# Sheet1without_res.net
KiCad netlist of a schematic drawn in Altium Designer
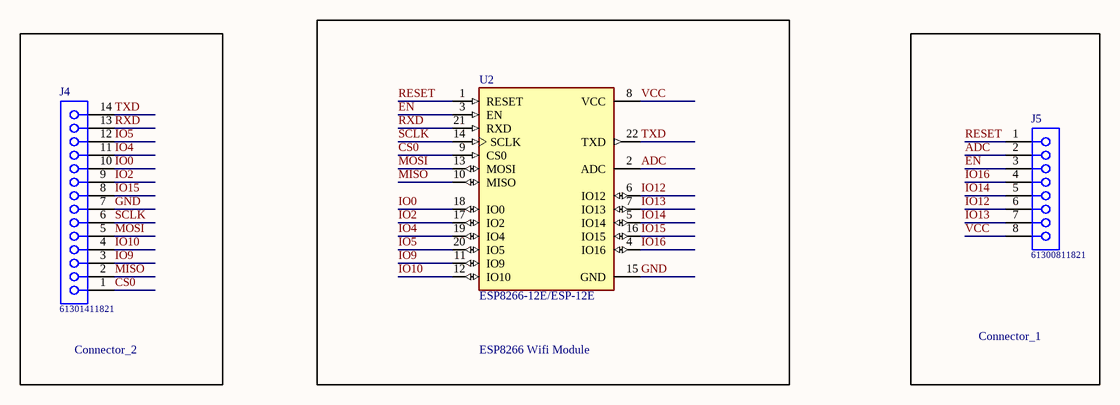
[diagram p0: Sheet1without_res.SchDoc]

(export (version "E")
  (design (tool "Eeschema 10.0.6"))
  (components
    (comp (ref "J4")
      (value "61301411821")
      (footprint "61301411821")
      (description "WR-PHD Socket Header, THT, pitch 2.54mm, Single Row, Vertical, 14p")
      (fields (field (name "MANUFACTURER") "Wurth Elektronik"))
      (libsource (lib "Altium_WR-PHD (rev20a) (2)") (part "61301411821"))
    )
    (comp (ref "J5")
      (value "61300811821")
      (footprint "61300811821")
      (description "WR-PHD Socket Header, THT, pitch 2.54mm, Single Row, Vertical, 8p")
      (fields (field (name "MANUFACTURER") "Wurth Elektronik"))
      (libsource (lib "Altium_WR-PHD (rev20a)") (part "61300811821"))
    )
    (comp (ref "U2")
      (value "ESP8266-12E/ESP-12E")
      (footprint "XCVR_ESP8266-12E/ESP-12E")
      (fields (field (name "MF") "AI-Thinker"))
      (libsource (lib "ESP8266-12E_ESP-12E") (part "ESP8266-12E/ESP-12E"))
    )
  )
  (nets
    (net (code "1") (name "/ADC") (class "Default")
      (node (ref "J5") (pin "2") (pinfunction "2_2") (pintype "passive"))
      (node (ref "U2") (pin "2") (pinfunction "ADC_2") (pintype "passive"))
    )
    (net (code "2") (name "/CS0") (class "Default")
      (node (ref "J4") (pin "1") (pinfunction "1_1") (pintype "passive"))
      (node (ref "U2") (pin "9") (pinfunction "CS0_9") (pintype "input"))
    )
    (net (code "3") (name "/EN") (class "Default")
      (node (ref "J5") (pin "3") (pinfunction "3_3") (pintype "passive"))
      (node (ref "U2") (pin "3") (pinfunction "EN_3") (pintype "input"))
    )
    (net (code "4") (name "/GND") (class "Default")
      (node (ref "J4") (pin "7") (pinfunction "7_7") (pintype "passive"))
      (node (ref "U2") (pin "15") (pinfunction "GND_15") (pintype "power_in"))
    )
    (net (code "5") (name "/IO0") (class "Default")
      (node (ref "J4") (pin "10") (pinfunction "10_10") (pintype "passive"))
      (node (ref "U2") (pin "18") (pinfunction "IO0_18") (pintype "bidirectional"))
    )
    (net (code "6") (name "/IO2") (class "Default")
      (node (ref "J4") (pin "9") (pinfunction "9_9") (pintype "passive"))
      (node (ref "U2") (pin "17") (pinfunction "IO2_17") (pintype "bidirectional"))
    )
    (net (code "7") (name "/IO4") (class "Default")
      (node (ref "J4") (pin "11") (pinfunction "11_11") (pintype "passive"))
      (node (ref "U2") (pin "19") (pinfunction "IO4_19") (pintype "bidirectional"))
    )
    (net (code "8") (name "/IO5") (class "Default")
      (node (ref "J4") (pin "12") (pinfunction "12_12") (pintype "passive"))
      (node (ref "U2") (pin "20") (pinfunction "IO5_20") (pintype "bidirectional"))
    )
    (net (code "9") (name "/IO9") (class "Default")
      (node (ref "J4") (pin "3") (pinfunction "3_3") (pintype "passive"))
      (node (ref "U2") (pin "11") (pinfunction "IO9_11") (pintype "bidirectional"))
    )
    (net (code "10") (name "/IO10") (class "Default")
      (node (ref "J4") (pin "4") (pinfunction "4_4") (pintype "passive"))
      (node (ref "U2") (pin "12") (pinfunction "IO10_12") (pintype "bidirectional"))
    )
    (net (code "11") (name "/IO12") (class "Default")
      (node (ref "J5") (pin "6") (pinfunction "6_6") (pintype "passive"))
      (node (ref "U2") (pin "6") (pinfunction "IO12_6") (pintype "bidirectional"))
    )
    (net (code "12") (name "/IO13") (class "Default")
      (node (ref "J5") (pin "7") (pinfunction "7_7") (pintype "passive"))
      (node (ref "U2") (pin "7") (pinfunction "IO13_7") (pintype "bidirectional"))
    )
    (net (code "13") (name "/IO14") (class "Default")
      (node (ref "J5") (pin "5") (pinfunction "5_5") (pintype "passive"))
      (node (ref "U2") (pin "5") (pinfunction "IO14_5") (pintype "bidirectional"))
    )
    (net (code "14") (name "/IO15") (class "Default")
      (node (ref "J4") (pin "8") (pinfunction "8_8") (pintype "passive"))
      (node (ref "U2") (pin "16") (pinfunction "IO15_16") (pintype "bidirectional"))
    )
    (net (code "15") (name "/IO16") (class "Default")
      (node (ref "J5") (pin "4") (pinfunction "4_4") (pintype "passive"))
      (node (ref "U2") (pin "4") (pinfunction "IO16_4") (pintype "bidirectional"))
    )
    (net (code "16") (name "/MISO") (class "Default")
      (node (ref "J4") (pin "2") (pinfunction "2_2") (pintype "passive"))
      (node (ref "U2") (pin "10") (pinfunction "MISO_10") (pintype "bidirectional"))
    )
    (net (code "17") (name "/MOSI") (class "Default")
      (node (ref "J4") (pin "5") (pinfunction "5_5") (pintype "passive"))
      (node (ref "U2") (pin "13") (pinfunction "MOSI_13") (pintype "bidirectional"))
    )
    (net (code "18") (name "/RESET") (class "Default")
      (node (ref "J5") (pin "1") (pinfunction "1_1") (pintype "passive"))
      (node (ref "U2") (pin "1") (pinfunction "RESET_1") (pintype "input"))
    )
    (net (code "19") (name "/RXD") (class "Default")
      (node (ref "J4") (pin "13") (pinfunction "13_13") (pintype "passive"))
      (node (ref "U2") (pin "21") (pinfunction "RXD_21") (pintype "input"))
    )
    (net (code "20") (name "/SCLK") (class "Default")
      (node (ref "J4") (pin "6") (pinfunction "6_6") (pintype "passive"))
      (node (ref "U2") (pin "14") (pinfunction "SCLK_14") (pintype "input"))
    )
    (net (code "21") (name "/TXD") (class "Default")
      (node (ref "J4") (pin "14") (pinfunction "14_14") (pintype "passive"))
      (node (ref "U2") (pin "22") (pinfunction "TXD_22") (pintype "output"))
    )
    (net (code "22") (name "/VCC") (class "Default")
      (node (ref "J5") (pin "8") (pinfunction "8_8") (pintype "passive"))
      (node (ref "U2") (pin "8") (pinfunction "VCC_8") (pintype "power_in"))
    )
  )
)
